# Connectors.net
KiCad netlist of a schematic drawn in Altium Designer
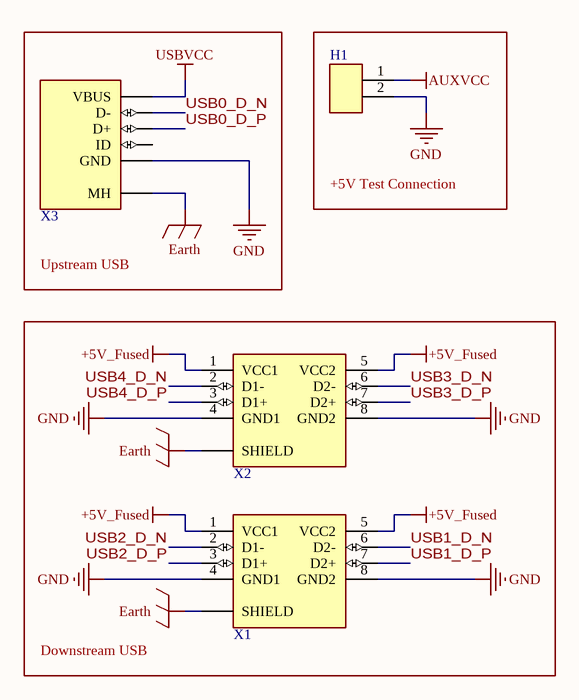
[diagram p0: Connectors.SchDoc]

(export (version "E")
  (design (tool "Eeschema 10.0.6"))
  (components
    (comp (ref "H1")
      (value "1x2 Header")
      (footprint "[Header] 1x2 Male")
      (description "2.54mm pitch")
      (libsource (lib "Connectors") (part "[Header] 1x2 Male"))
    )
    (comp (ref "X1")
      (value "USB-A")
      (footprint "[USB] Type-A Dual")
      (description "61400826021")
      (libsource (lib "Connectors") (part "[USB] Type-A Dual"))
    )
    (comp (ref "X2")
      (value "USB-A")
      (footprint "[USB] Type-A Dual")
      (description "61400826021")
      (libsource (lib "Connectors") (part "[USB] Type-A Dual"))
    )
    (comp (ref "X3")
      (value "[USB] Type-B Mini")
      (footprint "[USB] Type-B Mini")
      (description "MUSB-05-S-B-SM-A-K-TR")
      (libsource (lib "Connectors") (part "[USB] Type-B Mini"))
    )
  )
  (nets
    (net (code "1") (name "+5V_Fused") (class "Default")
      (node (ref "X1") (pin "1") (pinfunction "VCC1_1") (pintype "power_in"))
      (node (ref "X1") (pin "5") (pinfunction "VCC2_5") (pintype "power_in"))
      (node (ref "X2") (pin "1") (pinfunction "VCC1_1") (pintype "power_in"))
      (node (ref "X2") (pin "5") (pinfunction "VCC2_5") (pintype "power_in"))
    )
    (net (code "2") (name "/USB0_D_N") (class "Default")
      (node (ref "X3") (pin "2") (pinfunction "D-_2") (pintype "bidirectional"))
    )
    (net (code "3") (name "/USB0_D_P") (class "Default")
      (node (ref "X3") (pin "3") (pinfunction "D+_3") (pintype "bidirectional"))
    )
    (net (code "4") (name "/USB1_D_N") (class "Default")
      (node (ref "X1") (pin "6") (pinfunction "D2-_6") (pintype "bidirectional"))
    )
    (net (code "5") (name "/USB1_D_P") (class "Default")
      (node (ref "X1") (pin "7") (pinfunction "D2+_7") (pintype "bidirectional"))
    )
    (net (code "6") (name "/USB2_D_N") (class "Default")
      (node (ref "X1") (pin "2") (pinfunction "D1-_2") (pintype "bidirectional"))
    )
    (net (code "7") (name "/USB2_D_P") (class "Default")
      (node (ref "X1") (pin "3") (pinfunction "D1+_3") (pintype "bidirectional"))
    )
    (net (code "8") (name "/USB3_D_N") (class "Default")
      (node (ref "X2") (pin "6") (pinfunction "D2-_6") (pintype "bidirectional"))
    )
    (net (code "9") (name "/USB3_D_P") (class "Default")
      (node (ref "X2") (pin "7") (pinfunction "D2+_7") (pintype "bidirectional"))
    )
    (net (code "10") (name "/USB4_D_N") (class "Default")
      (node (ref "X2") (pin "2") (pinfunction "D1-_2") (pintype "bidirectional"))
    )
    (net (code "11") (name "/USB4_D_P") (class "Default")
      (node (ref "X2") (pin "3") (pinfunction "D1+_3") (pintype "bidirectional"))
    )
    (net (code "12") (name "AUXVCC") (class "Default") (node (ref "H1") (pin "1") (pintype "passive")))
    (net (code "13") (name "Earth") (class "Default")
      (node (ref "X1") (pin "MH") (pinfunction "SHIELD_MH") (pintype "passive"))
      (node (ref "X2") (pin "MH") (pinfunction "SHIELD_MH") (pintype "passive"))
      (node (ref "X3") (pin "MH") (pinfunction "MH_MH") (pintype "power_in"))
    )
    (net (code "14") (name "GND") (class "Default")
      (node (ref "H1") (pin "2") (pintype "passive"))
      (node (ref "X1") (pin "4") (pinfunction "GND1_4") (pintype "power_in"))
      (node (ref "X1") (pin "8") (pinfunction "GND2_8") (pintype "power_in"))
      (node (ref "X2") (pin "4") (pinfunction "GND1_4") (pintype "power_in"))
      (node (ref "X2") (pin "8") (pinfunction "GND2_8") (pintype "power_in"))
      (node (ref "X3") (pin "5") (pinfunction "GND_5") (pintype "power_in"))
    )
    (net (code "15") (name "USBVCC") (class "Default")
      (node (ref "X3") (pin "1") (pinfunction "VBUS_1") (pintype "power_in"))
    )
    (net (code "16") (name "unconnected-(X3-ID-Pad4)") (class "Default")
      (node (ref "X3") (pin "4") (pinfunction "ID_4") (pintype "bidirectional"))
    )
  )
)
